# rf_front_hf.net
KiCad netlist of a schematic drawn in EAGLE
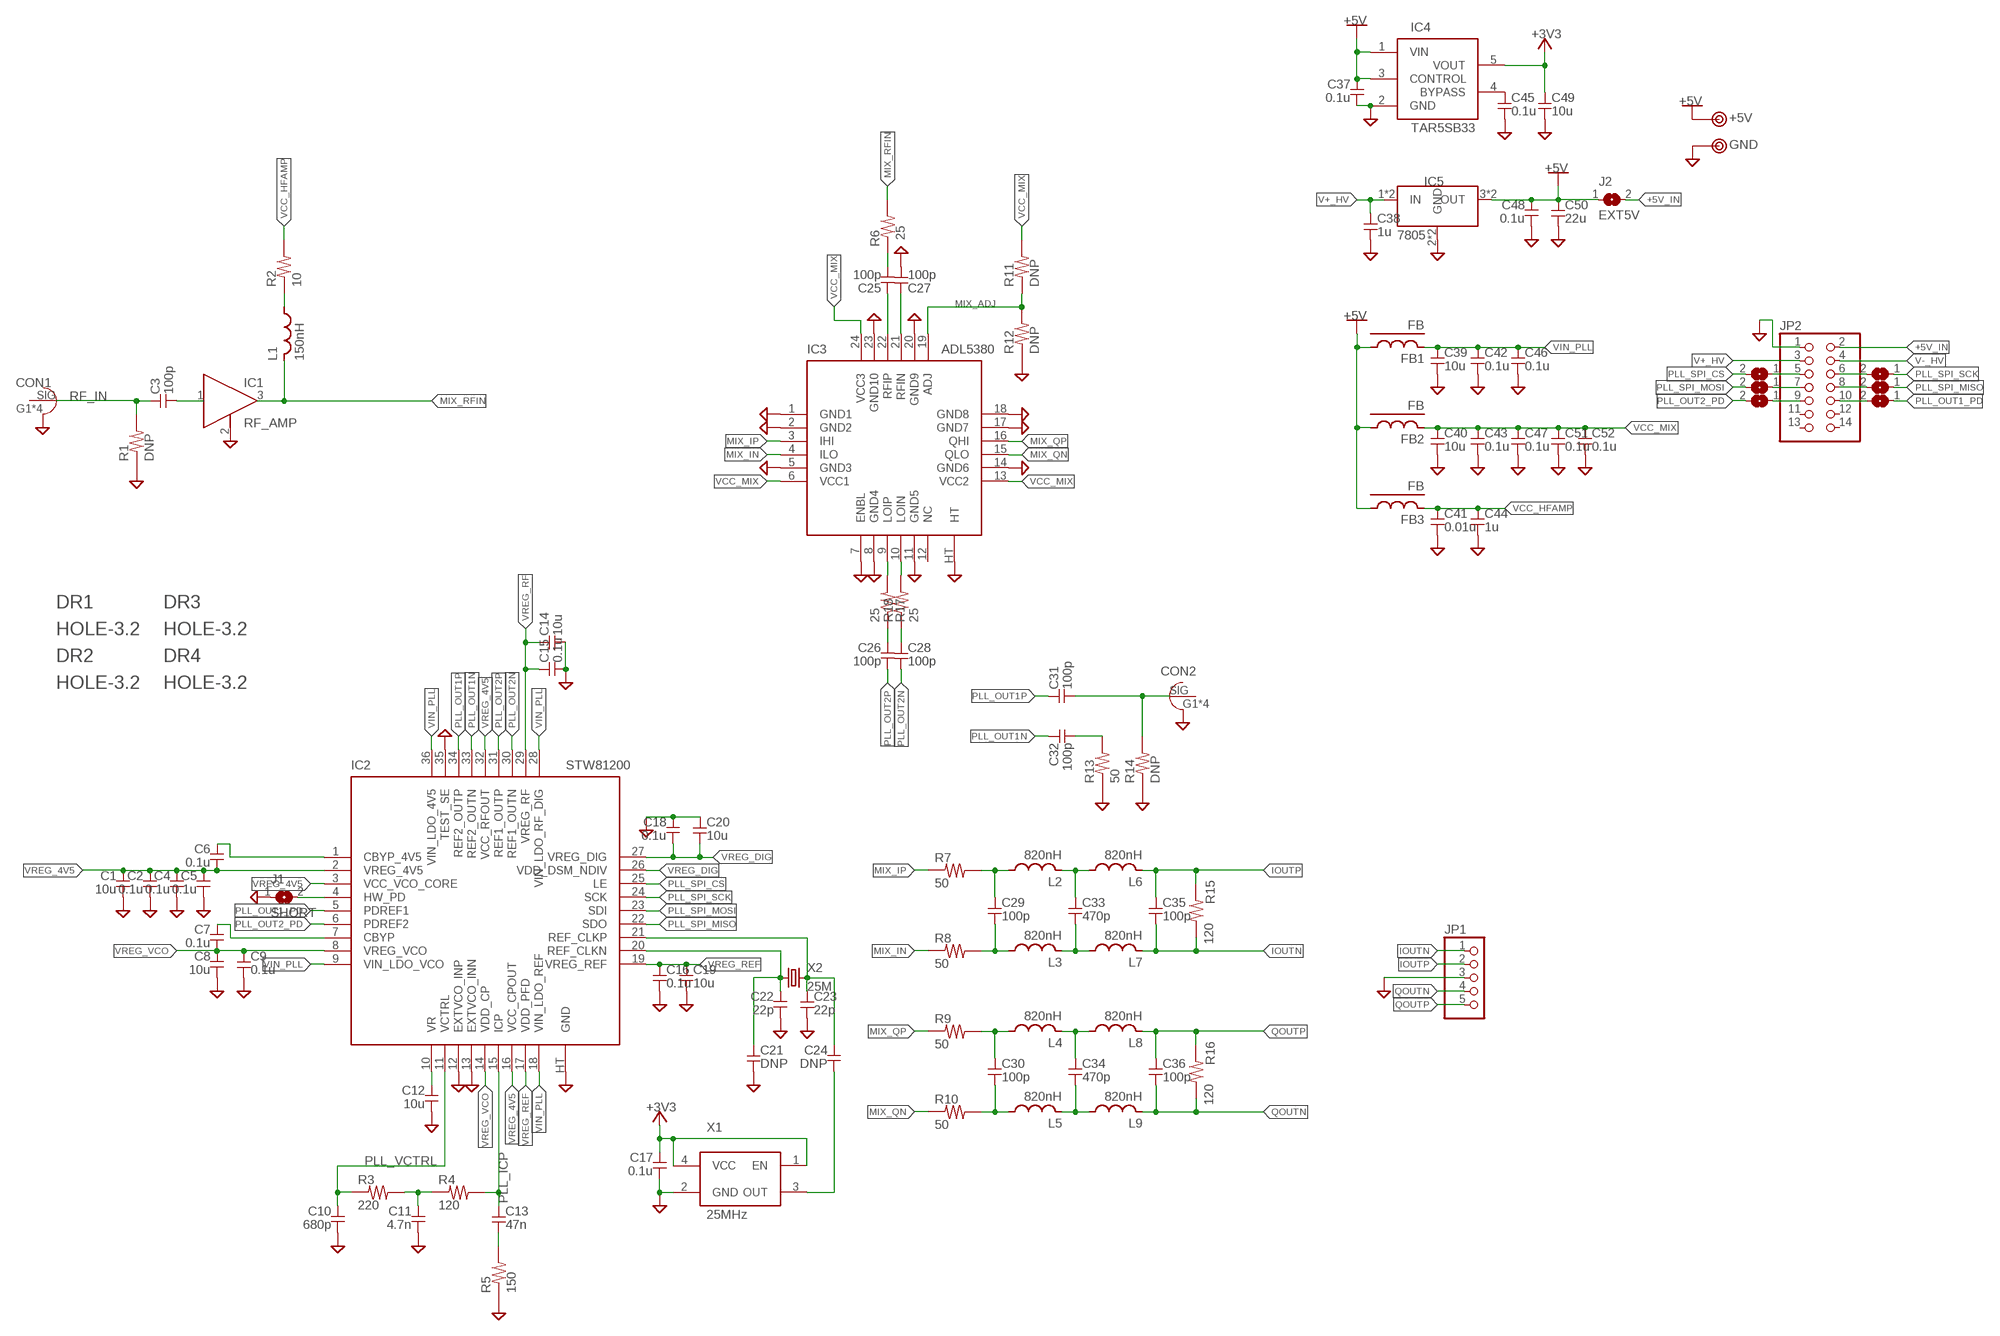
[diagram p0: schematic, sheet 1]

(export (version "E")
  (design (tool "Eeschema 10.0.6"))
  (components
    (comp (ref "C1")
      (value "10u")
      (footprint "eagle-import:1608")
      (libsource (lib "eagle-import") (part "C-1608"))
    )
    (comp (ref "C2")
      (value "0.1u")
      (footprint "eagle-import:1608")
      (libsource (lib "eagle-import") (part "C-1608"))
    )
    (comp (ref "C3")
      (value "100p")
      (footprint "eagle-import:1608")
      (libsource (lib "eagle-import") (part "C-1608"))
    )
    (comp (ref "C4")
      (value "0.1u")
      (footprint "eagle-import:1608")
      (libsource (lib "eagle-import") (part "C-1608"))
    )
    (comp (ref "C5")
      (value "0.1u")
      (footprint "eagle-import:1608")
      (libsource (lib "eagle-import") (part "C-1608"))
    )
    (comp (ref "C6")
      (value "0.1u")
      (footprint "eagle-import:1608")
      (libsource (lib "eagle-import") (part "C-1608"))
    )
    (comp (ref "C7")
      (value "0.1u")
      (footprint "eagle-import:1608")
      (libsource (lib "eagle-import") (part "C-1608"))
    )
    (comp (ref "C8")
      (value "10u")
      (footprint "eagle-import:1608")
      (libsource (lib "eagle-import") (part "C-1608"))
    )
    (comp (ref "C9")
      (value "0.1u")
      (footprint "eagle-import:1608")
      (libsource (lib "eagle-import") (part "C-1608"))
    )
    (comp (ref "C10")
      (value "680p")
      (footprint "eagle-import:1608")
      (libsource (lib "eagle-import") (part "C-1608"))
    )
    (comp (ref "C11")
      (value "4.7n")
      (footprint "eagle-import:1608")
      (libsource (lib "eagle-import") (part "C-1608"))
    )
    (comp (ref "C12")
      (value "10u")
      (footprint "eagle-import:1608")
      (libsource (lib "eagle-import") (part "C-1608"))
    )
    (comp (ref "C13")
      (value "47n")
      (footprint "eagle-import:1608")
      (libsource (lib "eagle-import") (part "C-1608"))
    )
    (comp (ref "C14")
      (value "10u")
      (footprint "eagle-import:1608")
      (libsource (lib "eagle-import") (part "C-1608"))
    )
    (comp (ref "C15")
      (value "0.1u")
      (footprint "eagle-import:1608")
      (libsource (lib "eagle-import") (part "C-1608"))
    )
    (comp (ref "C16")
      (value "0.1u")
      (footprint "eagle-import:1608")
      (libsource (lib "eagle-import") (part "C-1608"))
    )
    (comp (ref "C17")
      (value "0.1u")
      (footprint "eagle-import:1608")
      (libsource (lib "eagle-import") (part "C-1608"))
    )
    (comp (ref "C18")
      (value "0.1u")
      (footprint "eagle-import:1608")
      (libsource (lib "eagle-import") (part "C-1608"))
    )
    (comp (ref "C19")
      (value "10u")
      (footprint "eagle-import:1608")
      (libsource (lib "eagle-import") (part "C-1608"))
    )
    (comp (ref "C20")
      (value "10u")
      (footprint "eagle-import:1608")
      (libsource (lib "eagle-import") (part "C-1608"))
    )
    (comp (ref "C21")
      (value "DNP")
      (footprint "eagle-import:1608")
      (libsource (lib "eagle-import") (part "C-1608"))
    )
    (comp (ref "C22")
      (value "22p")
      (footprint "eagle-import:1608")
      (libsource (lib "eagle-import") (part "C-1608"))
    )
    (comp (ref "C23")
      (value "22p")
      (footprint "eagle-import:1608")
      (libsource (lib "eagle-import") (part "C-1608"))
    )
    (comp (ref "C24")
      (value "DNP")
      (footprint "eagle-import:1608")
      (libsource (lib "eagle-import") (part "C-1608"))
    )
    (comp (ref "C25")
      (value "100p")
      (footprint "eagle-import:1608")
      (libsource (lib "eagle-import") (part "C-1608"))
    )
    (comp (ref "C26")
      (value "100p")
      (footprint "eagle-import:1608")
      (libsource (lib "eagle-import") (part "C-1608"))
    )
    (comp (ref "C27")
      (value "100p")
      (footprint "eagle-import:1608")
      (libsource (lib "eagle-import") (part "C-1608"))
    )
    (comp (ref "C28")
      (value "100p")
      (footprint "eagle-import:1608")
      (libsource (lib "eagle-import") (part "C-1608"))
    )
    (comp (ref "C29")
      (value "100p")
      (footprint "eagle-import:1608")
      (libsource (lib "eagle-import") (part "C-1608"))
    )
    (comp (ref "C30")
      (value "100p")
      (footprint "eagle-import:1608")
      (libsource (lib "eagle-import") (part "C-1608"))
    )
    (comp (ref "C31")
      (value "100p")
      (footprint "eagle-import:1608")
      (libsource (lib "eagle-import") (part "C-1608"))
    )
    (comp (ref "C32")
      (value "100p")
      (footprint "eagle-import:1608")
      (libsource (lib "eagle-import") (part "C-1608"))
    )
    (comp (ref "C33")
      (value "470p")
      (footprint "eagle-import:1608")
      (libsource (lib "eagle-import") (part "C-1608"))
    )
    (comp (ref "C34")
      (value "470p")
      (footprint "eagle-import:1608")
      (libsource (lib "eagle-import") (part "C-1608"))
    )
    (comp (ref "C35")
      (value "100p")
      (footprint "eagle-import:1608")
      (libsource (lib "eagle-import") (part "C-1608"))
    )
    (comp (ref "C36")
      (value "100p")
      (footprint "eagle-import:1608")
      (libsource (lib "eagle-import") (part "C-1608"))
    )
    (comp (ref "C37")
      (value "0.1u")
      (footprint "eagle-import:1608")
      (libsource (lib "eagle-import") (part "C-1608"))
    )
    (comp (ref "C38")
      (value "1u")
      (footprint "eagle-import:1608")
      (libsource (lib "eagle-import") (part "C-1608"))
    )
    (comp (ref "C39")
      (value "10u")
      (footprint "eagle-import:2012")
      (libsource (lib "eagle-import") (part "C-2012"))
    )
    (comp (ref "C40")
      (value "10u")
      (footprint "eagle-import:2012")
      (libsource (lib "eagle-import") (part "C-2012"))
    )
    (comp (ref "C41")
      (value "0.01u")
      (footprint "eagle-import:1608")
      (libsource (lib "eagle-import") (part "C-1608"))
    )
    (comp (ref "C42")
      (value "0.1u")
      (footprint "eagle-import:1608")
      (libsource (lib "eagle-import") (part "C-1608"))
    )
    (comp (ref "C43")
      (value "0.1u")
      (footprint "eagle-import:1608")
      (libsource (lib "eagle-import") (part "C-1608"))
    )
    (comp (ref "C44")
      (value "1u")
      (footprint "eagle-import:1608")
      (libsource (lib "eagle-import") (part "C-1608"))
    )
    (comp (ref "C45")
      (value "0.1u")
      (footprint "eagle-import:1608")
      (libsource (lib "eagle-import") (part "C-1608"))
    )
    (comp (ref "C46")
      (value "0.1u")
      (footprint "eagle-import:1608")
      (libsource (lib "eagle-import") (part "C-1608"))
    )
    (comp (ref "C47")
      (value "0.1u")
      (footprint "eagle-import:1608")
      (libsource (lib "eagle-import") (part "C-1608"))
    )
    (comp (ref "C48")
      (value "0.1u")
      (footprint "eagle-import:1608")
      (libsource (lib "eagle-import") (part "C-1608"))
    )
    (comp (ref "C49")
      (value "10u")
      (footprint "eagle-import:1608")
      (libsource (lib "eagle-import") (part "C-1608"))
    )
    (comp (ref "C50")
      (value "22u")
      (footprint "eagle-import:3225")
      (libsource (lib "eagle-import") (part "C-3225"))
    )
    (comp (ref "C51")
      (value "0.1u")
      (footprint "eagle-import:1608")
      (libsource (lib "eagle-import") (part "C-1608"))
    )
    (comp (ref "C52")
      (value "0.1u")
      (footprint "eagle-import:1608")
      (libsource (lib "eagle-import") (part "C-1608"))
    )
    (comp (ref "CON1")
      (value "RF_IN")
      (footprint "eagle-import:SMA-EDGE")
      (libsource (lib "eagle-import") (part "SMA-142-0701-801"))
    )
    (comp (ref "CON2")
      (value "PLL_OUT")
      (footprint "eagle-import:SMA-EDGE")
      (libsource (lib "eagle-import") (part "SMA-142-0701-801"))
    )
    (comp (ref "DR1")
      (value "HOLE-3.2")
      (footprint "eagle-import:HOLE_3.2")
      (libsource (lib "eagle-import") (part "HOLE-3.2"))
    )
    (comp (ref "DR2")
      (value "HOLE-3.2")
      (footprint "eagle-import:HOLE_3.2")
      (libsource (lib "eagle-import") (part "HOLE-3.2"))
    )
    (comp (ref "DR3")
      (value "HOLE-3.2")
      (footprint "eagle-import:HOLE_3.2")
      (libsource (lib "eagle-import") (part "HOLE-3.2"))
    )
    (comp (ref "DR4")
      (value "HOLE-3.2")
      (footprint "eagle-import:HOLE_3.2")
      (libsource (lib "eagle-import") (part "HOLE-3.2"))
    )
    (comp (ref "FB1")
      (value "FB")
      (footprint "eagle-import:1608-J")
      (libsource (lib "eagle-import") (part "FB"))
    )
    (comp (ref "FB2")
      (value "FB")
      (footprint "eagle-import:1608-J")
      (libsource (lib "eagle-import") (part "FB"))
    )
    (comp (ref "FB3")
      (value "FB")
      (footprint "eagle-import:1608-J")
      (libsource (lib "eagle-import") (part "FB"))
    )
    (comp (ref "IC1")
      (value "RF_AMP")
      (footprint "eagle-import:SOT89")
      (libsource (lib "eagle-import") (part "RF_AMP"))
    )
    (comp (ref "IC2")
      (value "STW81200")
      (footprint "eagle-import:VFQFPN36")
      (libsource (lib "eagle-import") (part "STW81200"))
    )
    (comp (ref "IC3")
      (value "ADL5380")
      (footprint "eagle-import:LFCSP24")
      (libsource (lib "eagle-import") (part "ADL5380"))
    )
    (comp (ref "IC4")
      (value "TAR5SB33")
      (footprint "eagle-import:SOT23-5")
      (libsource (lib "eagle-import") (part "TAR5SB33"))
    )
    (comp (ref "IC5")
      (value "7805")
      (footprint "eagle-import:TO220-SOP-DUAL")
      (libsource (lib "eagle-import") (part "78X-3"))
    )
    (comp (ref "J1")
      (value "SHORT")
      (footprint "eagle-import:1608-J")
      (libsource (lib "eagle-import") (part "SJ-1608"))
    )
    (comp (ref "J2")
      (value "EXT5V")
      (footprint "eagle-import:1608-J")
      (libsource (lib "eagle-import") (part "SJ-1608"))
    )
    (comp (ref "J3")
      (value "CS")
      (footprint "eagle-import:1608-J")
      (libsource (lib "eagle-import") (part "SJ-1608"))
    )
    (comp (ref "J4")
      (value "MOSI")
      (footprint "eagle-import:1608-J")
      (libsource (lib "eagle-import") (part "SJ-1608"))
    )
    (comp (ref "J5")
      (value "PD2")
      (footprint "eagle-import:1608-J")
      (libsource (lib "eagle-import") (part "SJ-1608"))
    )
    (comp (ref "J6")
      (value "SCK")
      (footprint "eagle-import:1608-J")
      (libsource (lib "eagle-import") (part "SJ-1608"))
    )
    (comp (ref "J7")
      (value "MISO")
      (footprint "eagle-import:1608-J")
      (libsource (lib "eagle-import") (part "SJ-1608"))
    )
    (comp (ref "J8")
      (value "PD1")
      (footprint "eagle-import:1608-J")
      (libsource (lib "eagle-import") (part "SJ-1608"))
    )
    (comp (ref "JP1")
      (value "PINHD-1X5")
      (footprint "eagle-import:1X05")
      (libsource (lib "eagle-import") (part "PINHD-1X5"))
    )
    (comp (ref "JP2")
      (value "PINHD-2X7")
      (footprint "eagle-import:2X07")
      (libsource (lib "eagle-import") (part "PINHD-2X7"))
    )
    (comp (ref "L1")
      (value "150nH")
      (footprint "eagle-import:1608")
      (libsource (lib "eagle-import") (part "L-1608"))
    )
    (comp (ref "L2")
      (value "820nH")
      (footprint "eagle-import:1608")
      (libsource (lib "eagle-import") (part "L-1608"))
    )
    (comp (ref "L3")
      (value "820nH")
      (footprint "eagle-import:1608")
      (libsource (lib "eagle-import") (part "L-1608"))
    )
    (comp (ref "L4")
      (value "820nH")
      (footprint "eagle-import:1608")
      (libsource (lib "eagle-import") (part "L-1608"))
    )
    (comp (ref "L5")
      (value "820nH")
      (footprint "eagle-import:1608")
      (libsource (lib "eagle-import") (part "L-1608"))
    )
    (comp (ref "L6")
      (value "820nH")
      (footprint "eagle-import:1608")
      (libsource (lib "eagle-import") (part "L-1608"))
    )
    (comp (ref "L7")
      (value "820nH")
      (footprint "eagle-import:1608")
      (libsource (lib "eagle-import") (part "L-1608"))
    )
    (comp (ref "L8")
      (value "820nH")
      (footprint "eagle-import:1608")
      (libsource (lib "eagle-import") (part "L-1608"))
    )
    (comp (ref "L9")
      (value "820nH")
      (footprint "eagle-import:1608")
      (libsource (lib "eagle-import") (part "L-1608"))
    )
    (comp (ref "R1")
      (value "DNP")
      (footprint "eagle-import:1608")
      (libsource (lib "eagle-import") (part "R-1608"))
    )
    (comp (ref "R2")
      (value "10")
      (footprint "eagle-import:1608")
      (libsource (lib "eagle-import") (part "R-1608"))
    )
    (comp (ref "R3")
      (value "220")
      (footprint "eagle-import:1608")
      (libsource (lib "eagle-import") (part "R-1608"))
    )
    (comp (ref "R4")
      (value "120")
      (footprint "eagle-import:1608")
      (libsource (lib "eagle-import") (part "R-1608"))
    )
    (comp (ref "R5")
      (value "150")
      (footprint "eagle-import:1608")
      (libsource (lib "eagle-import") (part "R-1608"))
    )
    (comp (ref "R6")
      (value "25")
      (footprint "eagle-import:1608")
      (libsource (lib "eagle-import") (part "R-1608"))
    )
    (comp (ref "R7")
      (value "50")
      (footprint "eagle-import:1608")
      (libsource (lib "eagle-import") (part "R-1608"))
    )
    (comp (ref "R8")
      (value "50")
      (footprint "eagle-import:1608")
      (libsource (lib "eagle-import") (part "R-1608"))
    )
    (comp (ref "R9")
      (value "50")
      (footprint "eagle-import:1608")
      (libsource (lib "eagle-import") (part "R-1608"))
    )
    (comp (ref "R10")
      (value "50")
      (footprint "eagle-import:1608")
      (libsource (lib "eagle-import") (part "R-1608"))
    )
    (comp (ref "R11")
      (value "DNP")
      (footprint "eagle-import:1608")
      (libsource (lib "eagle-import") (part "R-1608"))
    )
    (comp (ref "R12")
      (value "DNP")
      (footprint "eagle-import:1608")
      (libsource (lib "eagle-import") (part "R-1608"))
    )
    (comp (ref "R13")
      (value "50")
      (footprint "eagle-import:1608")
      (libsource (lib "eagle-import") (part "R-1608"))
    )
    (comp (ref "R14")
      (value "DNP")
      (footprint "eagle-import:1608")
      (libsource (lib "eagle-import") (part "R-1608"))
    )
    (comp (ref "R15")
      (value "120")
      (footprint "eagle-import:1608")
      (libsource (lib "eagle-import") (part "R-1608"))
    )
    (comp (ref "R16")
      (value "120")
      (footprint "eagle-import:1608")
      (libsource (lib "eagle-import") (part "R-1608"))
    )
    (comp (ref "R17")
      (value "25")
      (footprint "eagle-import:1608")
      (libsource (lib "eagle-import") (part "R-1608"))
    )
    (comp (ref "R18")
      (value "25")
      (footprint "eagle-import:1608")
      (libsource (lib "eagle-import") (part "R-1608"))
    )
    (comp (ref "TP1")
      (value "+5V")
      (footprint "eagle-import:TESTPIN")
      (libsource (lib "eagle-import") (part "TESTPIN"))
    )
    (comp (ref "TP2")
      (value "GND")
      (footprint "eagle-import:TESTPIN")
      (libsource (lib "eagle-import") (part "TESTPIN"))
    )
    (comp (ref "X1")
      (value "25MHz")
      (footprint "eagle-import:KC3225")
      (libsource (lib "eagle-import") (part "OSC-KC3225"))
    )
    (comp (ref "X2")
      (value "25M")
      (footprint "eagle-import:HC49_S")
      (libsource (lib "eagle-import") (part "CRYSTALHC49S"))
    )
  )
  (nets
    (net (code "1") (name "+3V3") (class "Default")
      (node (ref "C17") (pin "1") (pinfunction "1_1") (pintype "passive"))
      (node (ref "C49") (pin "1") (pinfunction "1_1") (pintype "passive"))
      (node (ref "IC4") (pin "5") (pinfunction "VOUT_5") (pintype "power_in"))
      (node (ref "X1") (pin "1") (pinfunction "EN_1") (pintype "input"))
      (node (ref "X1") (pin "4") (pinfunction "VCC_4") (pintype "power_in"))
    )
    (net (code "2") (name "+5V") (class "Default")
      (node (ref "C37") (pin "1") (pinfunction "1_1") (pintype "passive"))
      (node (ref "C48") (pin "1") (pinfunction "1_1") (pintype "passive"))
      (node (ref "C50") (pin "1") (pinfunction "1_1") (pintype "passive"))
      (node (ref "FB1") (pin "1") (pinfunction "1_1") (pintype "passive"))
      (node (ref "FB2") (pin "1") (pinfunction "1_1") (pintype "passive"))
      (node (ref "FB3") (pin "1") (pinfunction "1_1") (pintype "passive"))
      (node (ref "IC4") (pin "1") (pinfunction "VIN_1") (pintype "power_in"))
      (node (ref "IC4") (pin "3") (pinfunction "CONTROL_3") (pintype "input"))
      (node (ref "IC5") (pin "3") (pinfunction "OUT_3") (pintype "output"))
      (node (ref "IC5") (pin "6") (pinfunction "OUT_6") (pintype "output"))
      (node (ref "J2") (pin "1") (pinfunction "1_1") (pintype "passive"))
      (node (ref "TP1") (pin "1") (pinfunction "1_1") (pintype "passive"))
    )
    (net (code "3") (name "+5V_IN") (class "Default")
      (node (ref "J2") (pin "2") (pinfunction "2_2") (pintype "passive"))
      (node (ref "JP2") (pin "2") (pinfunction "2_2") (pintype "passive"))
    )
    (net (code "4") (name "/MIX_ADJ") (class "Default")
      (node (ref "IC3") (pin "19") (pinfunction "ADJ_19") (pintype "bidirectional"))
      (node (ref "R11") (pin "1") (pinfunction "1_1") (pintype "passive"))
      (node (ref "R12") (pin "2") (pinfunction "2_2") (pintype "passive"))
    )
    (net (code "5") (name "/PLL_ICP") (class "Default")
      (node (ref "C13") (pin "1") (pinfunction "1_1") (pintype "passive"))
      (node (ref "IC2") (pin "15") (pinfunction "ICP_15") (pintype "output"))
      (node (ref "R4") (pin "2") (pinfunction "2_2") (pintype "passive"))
    )
    (net (code "6") (name "/PLL_VCTRL") (class "Default")
      (node (ref "C10") (pin "1") (pinfunction "1_1") (pintype "passive"))
      (node (ref "IC2") (pin "11") (pinfunction "VCTRL_11") (pintype "passive"))
      (node (ref "R3") (pin "1") (pinfunction "1_1") (pintype "passive"))
    )
    (net (code "7") (name "/RF_IN") (class "Default")
      (node (ref "C3") (pin "1") (pinfunction "1_1") (pintype "passive"))
      (node (ref "CON1") (pin "SIG") (pinfunction "SIG_SIG") (pintype "passive"))
      (node (ref "R1") (pin "2") (pinfunction "2_2") (pintype "passive"))
    )
    (net (code "8") (name "GND") (class "Default")
      (node (ref "C1") (pin "2") (pinfunction "2_2") (pintype "passive"))
      (node (ref "C10") (pin "2") (pinfunction "2_2") (pintype "passive"))
      (node (ref "C11") (pin "2") (pinfunction "2_2") (pintype "passive"))
      (node (ref "C12") (pin "2") (pinfunction "2_2") (pintype "passive"))
      (node (ref "C14") (pin "2") (pinfunction "2_2") (pintype "passive"))
      (node (ref "C15") (pin "2") (pinfunction "2_2") (pintype "passive"))
      (node (ref "C16") (pin "2") (pinfunction "2_2") (pintype "passive"))
      (node (ref "C17") (pin "2") (pinfunction "2_2") (pintype "passive"))
      (node (ref "C18") (pin "1") (pinfunction "1_1") (pintype "passive"))
      (node (ref "C19") (pin "2") (pinfunction "2_2") (pintype "passive"))
      (node (ref "C2") (pin "2") (pinfunction "2_2") (pintype "passive"))
      (node (ref "C20") (pin "1") (pinfunction "1_1") (pintype "passive"))
      (node (ref "C21") (pin "2") (pinfunction "2_2") (pintype "passive"))
      (node (ref "C22") (pin "2") (pinfunction "2_2") (pintype "passive"))
      (node (ref "C23") (pin "2") (pinfunction "2_2") (pintype "passive"))
      (node (ref "C27") (pin "2") (pinfunction "2_2") (pintype "passive"))
      (node (ref "C37") (pin "2") (pinfunction "2_2") (pintype "passive"))
      (node (ref "C38") (pin "2") (pinfunction "2_2") (pintype "passive"))
      (node (ref "C39") (pin "2") (pinfunction "2_2") (pintype "passive"))
      (node (ref "C4") (pin "2") (pinfunction "2_2") (pintype "passive"))
      (node (ref "C40") (pin "2") (pinfunction "2_2") (pintype "passive"))
      (node (ref "C41") (pin "2") (pinfunction "2_2") (pintype "passive"))
      (node (ref "C42") (pin "2") (pinfunction "2_2") (pintype "passive"))
      (node (ref "C43") (pin "2") (pinfunction "2_2") (pintype "passive"))
      (node (ref "C44") (pin "2") (pinfunction "2_2") (pintype "passive"))
      (node (ref "C45") (pin "2") (pinfunction "2_2") (pintype "passive"))
      (node (ref "C46") (pin "2") (pinfunction "2_2") (pintype "passive"))
      (node (ref "C47") (pin "2") (pinfunction "2_2") (pintype "passive"))
      (node (ref "C48") (pin "2") (pinfunction "2_2") (pintype "passive"))
      (node (ref "C49") (pin "2") (pinfunction "2_2") (pintype "passive"))
      (node (ref "C5") (pin "2") (pinfunction "2_2") (pintype "passive"))
      (node (ref "C50") (pin "2") (pinfunction "2_2") (pintype "passive"))
      (node (ref "C51") (pin "2") (pinfunction "2_2") (pintype "passive"))
      (node (ref "C52") (pin "2") (pinfunction "2_2") (pintype "passive"))
      (node (ref "C8") (pin "2") (pinfunction "2_2") (pintype "passive"))
      (node (ref "C9") (pin "2") (pinfunction "2_2") (pintype "passive"))
      (node (ref "CON1") (pin "G1") (pinfunction "GND_G1") (pintype "passive"))
      (node (ref "CON1") (pin "G2") (pinfunction "GND_G2") (pintype "passive"))
      (node (ref "CON1") (pin "G3") (pinfunction "GND_G3") (pintype "passive"))
      (node (ref "CON1") (pin "G4") (pinfunction "GND_G4") (pintype "passive"))
      (node (ref "CON2") (pin "G1") (pinfunction "GND_G1") (pintype "passive"))
      (node (ref "CON2") (pin "G2") (pinfunction "GND_G2") (pintype "passive"))
      (node (ref "CON2") (pin "G3") (pinfunction "GND_G3") (pintype "passive"))
      (node (ref "CON2") (pin "G4") (pinfunction "GND_G4") (pintype "passive"))
      (node (ref "IC1") (pin "2") (pinfunction "GND_2") (pintype "power_in"))
      (node (ref "IC2") (pin "12") (pinfunction "EXTVCO_INP_12") (pintype "input"))
      (node (ref "IC2") (pin "13") (pinfunction "EXTVCO_INN_13") (pintype "input"))
      (node (ref "IC2") (pin "35") (pinfunction "TEST_SE_35") (pintype "input"))
      (node (ref "IC2") (pin "HT") (pinfunction "GND_HT") (pintype "power_in"))
      (node (ref "IC3") (pin "1") (pinfunction "GND1_1") (pintype "power_in"))
      (node (ref "IC3") (pin "11") (pinfunction "GND5_11") (pintype "power_in"))
      (node (ref "IC3") (pin "14") (pinfunction "GND6_14") (pintype "power_in"))
      (node (ref "IC3") (pin "17") (pinfunction "GND7_17") (pintype "power_in"))
      (node (ref "IC3") (pin "18") (pinfunction "GND8_18") (pintype "power_in"))
      (node (ref "IC3") (pin "2") (pinfunction "GND2_2") (pintype "power_in"))
      (node (ref "IC3") (pin "20") (pinfunction "GND9_20") (pintype "power_in"))
      (node (ref "IC3") (pin "23") (pinfunction "GND10_23") (pintype "power_in"))
      (node (ref "IC3") (pin "5") (pinfunction "GND3_5") (pintype "power_in"))
      (node (ref "IC3") (pin "7") (pinfunction "ENBL_7") (pintype "input"))
      (node (ref "IC3") (pin "8") (pinfunction "GND4_8") (pintype "power_in"))
      (node (ref "IC3") (pin "HT") (pinfunction "HT_HT") (pintype "passive"))
      (node (ref "IC4") (pin "2") (pinfunction "GND_2") (pintype "power_in"))
      (node (ref "IC5") (pin "2") (pinfunction "GND_2") (pintype "power_in"))
      (node (ref "IC5") (pin "5") (pinfunction "GND_5") (pintype "power_in"))
      (node (ref "J1") (pin "1") (pinfunction "1_1") (pintype "passive"))
      (node (ref "JP1") (pin "3") (pinfunction "3_3") (pintype "passive"))
      (node (ref "JP2") (pin "1") (pinfunction "1_1") (pintype "passive"))
      (node (ref "R1") (pin "1") (pinfunction "1_1") (pintype "passive"))
      (node (ref "R12") (pin "1") (pinfunction "1_1") (pintype "passive"))
      (node (ref "R13") (pin "1") (pinfunction "1_1") (pintype "passive"))
      (node (ref "R14") (pin "1") (pinfunction "1_1") (pintype "passive"))
      (node (ref "R5") (pin "1") (pinfunction "1_1") (pintype "passive"))
      (node (ref "TP2") (pin "1") (pinfunction "1_1") (pintype "passive"))
      (node (ref "X1") (pin "2") (pinfunction "GND_2") (pintype "power_in"))
    )
    (net (code "9") (name "IOUTN") (class "Default")
      (node (ref "C35") (pin "2") (pinfunction "2_2") (pintype "passive"))
      (node (ref "JP1") (pin "1") (pinfunction "1_1") (pintype "passive"))
      (node (ref "L7") (pin "2") (pinfunction "2_2") (pintype "passive"))
      (node (ref "R15") (pin "1") (pinfunction "1_1") (pintype "passive"))
    )
    (net (code "10") (name "IOUTP") (class "Default")
      (node (ref "C35") (pin "1") (pinfunction "1_1") (pintype "passive"))
      (node (ref "JP1") (pin "2") (pinfunction "2_2") (pintype "passive"))
      (node (ref "L6") (pin "2") (pinfunction "2_2") (pintype "passive"))
      (node (ref "R15") (pin "2") (pinfunction "2_2") (pintype "passive"))
    )
    (net (code "11") (name "MIX_IN") (class "Default")
      (node (ref "IC3") (pin "4") (pinfunction "ILO_4") (pintype "output"))
      (node (ref "R8") (pin "1") (pinfunction "1_1") (pintype "passive"))
    )
    (net (code "12") (name "MIX_IP") (class "Default")
      (node (ref "IC3") (pin "3") (pinfunction "IHI_3") (pintype "output"))
      (node (ref "R7") (pin "1") (pinfunction "1_1") (pintype "passive"))
    )
    (net (code "13") (name "MIX_QN") (class "Default")
      (node (ref "IC3") (pin "15") (pinfunction "QLO_15") (pintype "output"))
      (node (ref "R10") (pin "1") (pinfunction "1_1") (pintype "passive"))
    )
    (net (code "14") (name "MIX_QP") (class "Default")
      (node (ref "IC3") (pin "16") (pinfunction "QHI_16") (pintype "output"))
      (node (ref "R9") (pin "1") (pinfunction "1_1") (pintype "passive"))
    )
    (net (code "15") (name "MIX_RFIN") (class "Default")
      (node (ref "IC1") (pin "3") (pinfunction "OUT_3") (pintype "output"))
      (node (ref "L1") (pin "2") (pinfunction "2_2") (pintype "passive"))
      (node (ref "R6") (pin "2") (pinfunction "2_2") (pintype "passive"))
    )
    (net (code "16") (name "Net-(C11-Pad1)") (class "Default")
      (node (ref "C11") (pin "1") (pinfunction "1_1") (pintype "passive"))
      (node (ref "R3") (pin "2") (pinfunction "2_2") (pintype "passive"))
      (node (ref "R4") (pin "1") (pinfunction "1_1") (pintype "passive"))
    )
    (net (code "17") (name "Net-(C13-Pad2)") (class "Default")
      (node (ref "C13") (pin "2") (pinfunction "2_2") (pintype "passive"))
      (node (ref "R5") (pin "2") (pinfunction "2_2") (pintype "passive"))
    )
    (net (code "18") (name "Net-(C25-Pad2)") (class "Default")
      (node (ref "C25") (pin "2") (pinfunction "2_2") (pintype "passive"))
      (node (ref "R6") (pin "1") (pinfunction "1_1") (pintype "passive"))
    )
    (net (code "19") (name "Net-(C26-Pad1)") (class "Default")
      (node (ref "C26") (pin "1") (pinfunction "1_1") (pintype "passive"))
      (node (ref "R17") (pin "1") (pinfunction "1_1") (pintype "passive"))
    )
    (net (code "20") (name "Net-(C28-Pad1)") (class "Default")
      (node (ref "C28") (pin "1") (pinfunction "1_1") (pintype "passive"))
      (node (ref "R18") (pin "1") (pinfunction "1_1") (pintype "passive"))
    )
    (net (code "21") (name "Net-(C29-Pad1)") (class "Default")
      (node (ref "C29") (pin "1") (pinfunction "1_1") (pintype "passive"))
      (node (ref "L2") (pin "1") (pinfunction "1_1") (pintype "passive"))
      (node (ref "R7") (pin "2") (pinfunction "2_2") (pintype "passive"))
    )
    (net (code "22") (name "Net-(C29-Pad2)") (class "Default")
      (node (ref "C29") (pin "2") (pinfunction "2_2") (pintype "passive"))
      (node (ref "L3") (pin "1") (pinfunction "1_1") (pintype "passive"))
      (node (ref "R8") (pin "2") (pinfunction "2_2") (pintype "passive"))
    )
    (net (code "23") (name "Net-(C30-Pad1)") (class "Default")
      (node (ref "C30") (pin "1") (pinfunction "1_1") (pintype "passive"))
      (node (ref "L4") (pin "1") (pinfunction "1_1") (pintype "passive"))
      (node (ref "R9") (pin "2") (pinfunction "2_2") (pintype "passive"))
    )
    (net (code "24") (name "Net-(C30-Pad2)") (class "Default")
      (node (ref "C30") (pin "2") (pinfunction "2_2") (pintype "passive"))
      (node (ref "L5") (pin "1") (pinfunction "1_1") (pintype "passive"))
      (node (ref "R10") (pin "2") (pinfunction "2_2") (pintype "passive"))
    )
    (net (code "25") (name "Net-(C31-Pad2)") (class "Default")
      (node (ref "C31") (pin "2") (pinfunction "2_2") (pintype "passive"))
      (node (ref "CON2") (pin "SIG") (pinfunction "SIG_SIG") (pintype "passive"))
      (node (ref "R14") (pin "2") (pinfunction "2_2") (pintype "passive"))
    )
    (net (code "26") (name "Net-(C32-Pad2)") (class "Default")
      (node (ref "C32") (pin "2") (pinfunction "2_2") (pintype "passive"))
      (node (ref "R13") (pin "2") (pinfunction "2_2") (pintype "passive"))
    )
    (net (code "27") (name "Net-(C33-Pad1)") (class "Default")
      (node (ref "C33") (pin "1") (pinfunction "1_1") (pintype "passive"))
      (node (ref "L2") (pin "2") (pinfunction "2_2") (pintype "passive"))
      (node (ref "L6") (pin "1") (pinfunction "1_1") (pintype "passive"))
    )
    (net (code "28") (name "Net-(C33-Pad2)") (class "Default")
      (node (ref "C33") (pin "2") (pinfunction "2_2") (pintype "passive"))
      (node (ref "L3") (pin "2") (pinfunction "2_2") (pintype "passive"))
      (node (ref "L7") (pin "1") (pinfunction "1_1") (pintype "passive"))
    )
    (net (code "29") (name "Net-(C34-Pad1)") (class "Default")
      (node (ref "C34") (pin "1") (pinfunction "1_1") (pintype "passive"))
      (node (ref "L4") (pin "2") (pinfunction "2_2") (pintype "passive"))
      (node (ref "L8") (pin "1") (pinfunction "1_1") (pintype "passive"))
    )
    (net (code "30") (name "Net-(C34-Pad2)") (class "Default")
      (node (ref "C34") (pin "2") (pinfunction "2_2") (pintype "passive"))
      (node (ref "L5") (pin "2") (pinfunction "2_2") (pintype "passive"))
      (node (ref "L9") (pin "1") (pinfunction "1_1") (pintype "passive"))
    )
    (net (code "31") (name "Net-(IC1-IN)") (class "Default")
      (node (ref "C3") (pin "2") (pinfunction "2_2") (pintype "passive"))
      (node (ref "IC1") (pin "1") (pinfunction "IN_1") (pintype "input"))
    )
    (net (code "32") (name "Net-(IC2-CBYP)") (class "Default")
      (node (ref "C7") (pin "1") (pinfunction "1_1") (pintype "passive"))
      (node (ref "IC2") (pin "7") (pinfunction "CBYP_7") (pintype "passive"))
    )
    (net (code "33") (name "Net-(IC2-CBYP_4V5)") (class "Default")
      (node (ref "C6") (pin "1") (pinfunction "1_1") (pintype "passive"))
      (node (ref "IC2") (pin "1") (pinfunction "CBYP_4V5_1") (pintype "passive"))
    )
    (net (code "34") (name "Net-(IC2-HW_PD)") (class "Default")
      (node (ref "IC2") (pin "4") (pinfunction "HW_PD_4") (pintype "input"))
      (node (ref "J1") (pin "2") (pinfunction "2_2") (pintype "passive"))
    )
    (net (code "35") (name "Net-(IC2-REF_CLKN)") (class "Default")
      (node (ref "C21") (pin "1") (pinfunction "1_1") (pintype "passive"))
      (node (ref "C22") (pin "1") (pinfunction "1_1") (pintype "passive"))
      (node (ref "IC2") (pin "20") (pinfunction "REF_CLKN_20") (pintype "input"))
      (node (ref "X2") (pin "1") (pinfunction "1_1") (pintype "passive"))
    )
    (net (code "36") (name "Net-(IC2-REF_CLKP)") (class "Default")
      (node (ref "C23") (pin "1") (pinfunction "1_1") (pintype "passive"))
      (node (ref "C24") (pin "1") (pinfunction "1_1") (pintype "passive"))
      (node (ref "IC2") (pin "21") (pinfunction "REF_CLKP_21") (pintype "input"))
      (node (ref "X2") (pin "2") (pinfunction "2_2") (pintype "passive"))
    )
    (net (code "37") (name "Net-(IC2-VR)") (class "Default")
      (node (ref "C12") (pin "1") (pinfunction "1_1") (pintype "passive"))
      (node (ref "IC2") (pin "10") (pinfunction "VR_10") (pintype "passive"))
    )
    (net (code "38") (name "Net-(IC3-LOIN)") (class "Default")
      (node (ref "IC3") (pin "10") (pinfunction "LOIN_10") (pintype "input"))
      (node (ref "R18") (pin "2") (pinfunction "2_2") (pintype "passive"))
    )
    (net (code "39") (name "Net-(IC3-LOIP)") (class "Default")
      (node (ref "IC3") (pin "9") (pinfunction "LOIP_9") (pintype "input"))
      (node (ref "R17") (pin "2") (pinfunction "2_2") (pintype "passive"))
    )
    (net (code "40") (name "Net-(IC3-RFIN)") (class "Default")
      (node (ref "C27") (pin "1") (pinfunction "1_1") (pintype "passive"))
      (node (ref "IC3") (pin "21") (pinfunction "RFIN_21") (pintype "input"))
    )
    (net (code "41") (name "Net-(IC3-RFIP)") (class "Default")
      (node (ref "C25") (pin "1") (pinfunction "1_1") (pintype "passive"))
      (node (ref "IC3") (pin "22") (pinfunction "RFIP_22") (pintype "input"))
    )
    (net (code "42") (name "Net-(IC4-BYPASS)") (class "Default")
      (node (ref "C45") (pin "1") (pinfunction "1_1") (pintype "passive"))
      (node (ref "IC4") (pin "4") (pinfunction "BYPASS_4") (pintype "passive"))
    )
    (net (code "43") (name "Net-(J3-Pad1)") (class "Default")
      (node (ref "J3") (pin "1") (pinfunction "1_1") (pintype "passive"))
      (node (ref "JP2") (pin "5") (pinfunction "5_5") (pintype "passive"))
    )
    (net (code "44") (name "Net-(J4-Pad1)") (class "Default")
      (node (ref "J4") (pin "1") (pinfunction "1_1") (pintype "passive"))
      (node (ref "JP2") (pin "7") (pinfunction "7_7") (pintype "passive"))
    )
    (net (code "45") (name "Net-(J5-Pad1)") (class "Default")
      (node (ref "J5") (pin "1") (pinfunction "1_1") (pintype "passive"))
      (node (ref "JP2") (pin "9") (pinfunction "9_9") (pintype "passive"))
    )
    (net (code "46") (name "Net-(J6-Pad2)") (class "Default")
      (node (ref "J6") (pin "2") (pinfunction "2_2") (pintype "passive"))
      (node (ref "JP2") (pin "6") (pinfunction "6_6") (pintype "passive"))
    )
    (net (code "47") (name "Net-(J7-Pad2)") (class "Default")
      (node (ref "J7") (pin "2") (pinfunction "2_2") (pintype "passive"))
      (node (ref "JP2") (pin "8") (pinfunction "8_8") (pintype "passive"))
    )
    (net (code "48") (name "Net-(J8-Pad2)") (class "Default")
      (node (ref "J8") (pin "2") (pinfunction "2_2") (pintype "passive"))
      (node (ref "JP2") (pin "10") (pinfunction "10_10") (pintype "passive"))
    )
    (net (code "49") (name "Net-(L1-Pad1)") (class "Default")
      (node (ref "L1") (pin "1") (pinfunction "1_1") (pintype "passive"))
      (node (ref "R2") (pin "1") (pinfunction "1_1") (pintype "passive"))
    )
    (net (code "50") (name "Net-(X1-OUT)") (class "Default")
      (node (ref "C24") (pin "2") (pinfunction "2_2") (pintype "passive"))
      (node (ref "X1") (pin "3") (pinfunction "OUT_3") (pintype "output"))
    )
    (net (code "51") (name "PLL_OUT1N") (class "Default")
      (node (ref "C32") (pin "1") (pinfunction "1_1") (pintype "passive"))
      (node (ref "IC2") (pin "33") (pinfunction "REF2_OUTN_33") (pintype "passive"))
    )
    (net (code "52") (name "PLL_OUT1P") (class "Default")
      (node (ref "C31") (pin "1") (pinfunction "1_1") (pintype "passive"))
      (node (ref "IC2") (pin "34") (pinfunction "REF2_OUTP_34") (pintype "passive"))
    )
    (net (code "53") (name "PLL_OUT1_PD") (class "Default")
      (node (ref "IC2") (pin "5") (pinfunction "PDREF1_5") (pintype "input"))
      (node (ref "J8") (pin "1") (pinfunction "1_1") (pintype "passive"))
    )
    (net (code "54") (name "PLL_OUT2N") (class "Default")
      (node (ref "C28") (pin "2") (pinfunction "2_2") (pintype "passive"))
      (node (ref "IC2") (pin "30") (pinfunction "REF1_OUTN_30") (pintype "output"))
    )
    (net (code "55") (name "PLL_OUT2P") (class "Default")
      (node (ref "C26") (pin "2") (pinfunction "2_2") (pintype "passive"))
      (node (ref "IC2") (pin "31") (pinfunction "REF1_OUTP_31") (pintype "output"))
    )
    (net (code "56") (name "PLL_OUT2_PD") (class "Default")
      (node (ref "IC2") (pin "6") (pinfunction "PDREF2_6") (pintype "input"))
      (node (ref "J5") (pin "2") (pinfunction "2_2") (pintype "passive"))
    )
    (net (code "57") (name "PLL_SPI_CS") (class "Default")
      (node (ref "IC2") (pin "25") (pinfunction "LE_25") (pintype "bidirectional"))
      (node (ref "J3") (pin "2") (pinfunction "2_2") (pintype "passive"))
    )
    (net (code "58") (name "PLL_SPI_MISO") (class "Default")
      (node (ref "IC2") (pin "22") (pinfunction "SDO_22") (pintype "bidirectional"))
      (node (ref "J7") (pin "1") (pinfunction "1_1") (pintype "passive"))
    )
    (net (code "59") (name "PLL_SPI_MOSI") (class "Default")
      (node (ref "IC2") (pin "23") (pinfunction "SDI_23") (pintype "bidirectional"))
      (node (ref "J4") (pin "2") (pinfunction "2_2") (pintype "passive"))
    )
    (net (code "60") (name "PLL_SPI_SCK") (class "Default")
      (node (ref "IC2") (pin "24") (pinfunction "SCK_24") (pintype "bidirectional"))
      (node (ref "J6") (pin "1") (pinfunction "1_1") (pintype "passive"))
    )
    (net (code "61") (name "QOUTN") (class "Default")
      (node (ref "C36") (pin "2") (pinfunction "2_2") (pintype "passive"))
      (node (ref "JP1") (pin "4") (pinfunction "4_4") (pintype "passive"))
      (node (ref "L9") (pin "2") (pinfunction "2_2") (pintype "passive"))
      (node (ref "R16") (pin "1") (pinfunction "1_1") (pintype "passive"))
    )
    (net (code "62") (name "QOUTP") (class "Default")
      (node (ref "C36") (pin "1") (pinfunction "1_1") (pintype "passive"))
      (node (ref "JP1") (pin "5") (pinfunction "5_5") (pintype "passive"))
      (node (ref "L8") (pin "2") (pinfunction "2_2") (pintype "passive"))
      (node (ref "R16") (pin "2") (pinfunction "2_2") (pintype "passive"))
    )
    (net (code "63") (name "V+_HV") (class "Default")
      (node (ref "C38") (pin "1") (pinfunction "1_1") (pintype "passive"))
      (node (ref "IC5") (pin "1") (pinfunction "IN_1") (pintype "power_in"))
      (node (ref "IC5") (pin "4") (pinfunction "IN_4") (pintype "power_in"))
      (node (ref "JP2") (pin "3") (pinfunction "3_3") (pintype "passive"))
    )
    (net (code "64") (name "V-_HV") (class "Default")
      (node (ref "JP2") (pin "4") (pinfunction "4_4") (pintype "passive"))
    )
    (net (code "65") (name "VCC_HFAMP") (class "Default")
      (node (ref "C41") (pin "1") (pinfunction "1_1") (pintype "passive"))
      (node (ref "C44") (pin "1") (pinfunction "1_1") (pintype "passive"))
      (node (ref "FB3") (pin "2") (pinfunction "2_2") (pintype "passive"))
      (node (ref "R2") (pin "2") (pinfunction "2_2") (pintype "passive"))
    )
    (net (code "66") (name "VCC_MIX") (class "Default")
      (node (ref "C40") (pin "1") (pinfunction "1_1") (pintype "passive"))
      (node (ref "C43") (pin "1") (pinfunction "1_1") (pintype "passive"))
      (node (ref "C47") (pin "1") (pinfunction "1_1") (pintype "passive"))
      (node (ref "C51") (pin "1") (pinfunction "1_1") (pintype "passive"))
      (node (ref "C52") (pin "1") (pinfunction "1_1") (pintype "passive"))
      (node (ref "FB2") (pin "2") (pinfunction "2_2") (pintype "passive"))
      (node (ref "IC3") (pin "13") (pinfunction "VCC2_13") (pintype "power_in"))
      (node (ref "IC3") (pin "24") (pinfunction "VCC3_24") (pintype "power_in"))
      (node (ref "IC3") (pin "6") (pinfunction "VCC1_6") (pintype "power_in"))
      (node (ref "R11") (pin "2") (pinfunction "2_2") (pintype "passive"))
    )
    (net (code "67") (name "VIN_PLL") (class "Default")
      (node (ref "C39") (pin "1") (pinfunction "1_1") (pintype "passive"))
      (node (ref "C42") (pin "1") (pinfunction "1_1") (pintype "passive"))
      (node (ref "C46") (pin "1") (pinfunction "1_1") (pintype "passive"))
      (node (ref "FB1") (pin "2") (pinfunction "2_2") (pintype "passive"))
      (node (ref "IC2") (pin "18") (pinfunction "VIN_LDO_REF_18") (pintype "power_in"))
      (node (ref "IC2") (pin "28") (pinfunction "VIN_LDO_RF_DIG_28") (pintype "power_in"))
      (node (ref "IC2") (pin "36") (pinfunction "VIN_LDO_4V5_36") (pintype "power_in"))
      (node (ref "IC2") (pin "9") (pinfunction "VIN_LDO_VCO_9") (pintype "power_in"))
    )
    (net (code "68") (name "VREG_4V5") (class "Default")
      (node (ref "C1") (pin "1") (pinfunction "1_1") (pintype "passive"))
      (node (ref "C2") (pin "1") (pinfunction "1_1") (pintype "passive"))
      (node (ref "C4") (pin "1") (pinfunction "1_1") (pintype "passive"))
      (node (ref "C5") (pin "1") (pinfunction "1_1") (pintype "passive"))
      (node (ref "C6") (pin "2") (pinfunction "2_2") (pintype "passive"))
      (node (ref "IC2") (pin "16") (pinfunction "VCC_CPOUT_16") (pintype "power_in"))
      (node (ref "IC2") (pin "2") (pinfunction "VREG_4V5_2") (pintype "passive"))
      (node (ref "IC2") (pin "3") (pinfunction "VCC_VCO_CORE_3") (pintype "power_in"))
      (node (ref "IC2") (pin "32") (pinfunction "VCC_RFOUT_32") (pintype "power_in"))
    )
    (net (code "69") (name "VREG_DIG") (class "Default")
      (node (ref "C18") (pin "2") (pinfunction "2_2") (pintype "passive"))
      (node (ref "C20") (pin "2") (pinfunction "2_2") (pintype "passive"))
      (node (ref "IC2") (pin "26") (pinfunction "VDD_DSM_NDIV_26") (pintype "power_in"))
      (node (ref "IC2") (pin "27") (pinfunction "VREG_DIG_27") (pintype "passive"))
    )
    (net (code "70") (name "VREG_REF") (class "Default")
      (node (ref "C16") (pin "1") (pinfunction "1_1") (pintype "passive"))
      (node (ref "C19") (pin "1") (pinfunction "1_1") (pintype "passive"))
      (node (ref "IC2") (pin "17") (pinfunction "VDD_PFD_17") (pintype "power_in"))
      (node (ref "IC2") (pin "19") (pinfunction "VREG_REF_19") (pintype "passive"))
    )
    (net (code "71") (name "VREG_RF") (class "Default")
      (node (ref "C14") (pin "1") (pinfunction "1_1") (pintype "passive"))
      (node (ref "C15") (pin "1") (pinfunction "1_1") (pintype "passive"))
      (node (ref "IC2") (pin "29") (pinfunction "VREG_RF_29") (pintype "passive"))
    )
    (net (code "72") (name "VREG_VCO") (class "Default")
      (node (ref "C7") (pin "2") (pinfunction "2_2") (pintype "passive"))
      (node (ref "C8") (pin "1") (pinfunction "1_1") (pintype "passive"))
      (node (ref "C9") (pin "1") (pinfunction "1_1") (pintype "passive"))
      (node (ref "IC2") (pin "14") (pinfunction "VDD_CP_14") (pintype "power_in"))
      (node (ref "IC2") (pin "8") (pinfunction "VREG_VCO_8") (pintype "passive"))
    )
    (net (code "73") (name "unconnected-(IC3-NC-Pad12)") (class "Default")
      (node (ref "IC3") (pin "12") (pinfunction "NC_12") (pintype "passive"))
    )
    (net (code "74") (name "unconnected-(JP2-Pad11)") (class "Default")
      (node (ref "JP2") (pin "11") (pinfunction "11_11") (pintype "passive"))
    )
    (net (code "75") (name "unconnected-(JP2-Pad12)") (class "Default")
      (node (ref "JP2") (pin "12") (pinfunction "12_12") (pintype "passive"))
    )
    (net (code "76") (name "unconnected-(JP2-Pad13)") (class "Default")
      (node (ref "JP2") (pin "13") (pinfunction "13_13") (pintype "passive"))
    )
    (net (code "77") (name "unconnected-(JP2-Pad14)") (class "Default")
      (node (ref "JP2") (pin "14") (pinfunction "14_14") (pintype "passive"))
    )
  )
)
